# untitled.net
KiCad netlist of a schematic drawn in EAGLE
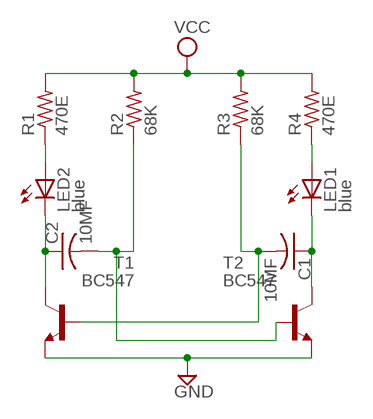
[diagram p0: schematic, sheet 1]

(export (version "E")
  (design (tool "Eeschema 10.0.6"))
  (components
    (comp (ref "C1")
      (value "10MF")
      (footprint "eagle-import:C050-024X044")
      (libsource (lib "eagle-import") (part "C-US050-024X044"))
    )
    (comp (ref "C2")
      (value "10MF")
      (footprint "eagle-import:C050-024X044")
      (libsource (lib "eagle-import") (part "C-US050-024X044"))
    )
    (comp (ref "LED1")
      (value "blue")
      (footprint "eagle-import:LED5MM")
      (libsource (lib "eagle-import") (part "LED5MM"))
    )
    (comp (ref "LED2")
      (value "blue")
      (footprint "eagle-import:LED5MM")
      (libsource (lib "eagle-import") (part "LED5MM"))
    )
    (comp (ref "R1")
      (value "470E")
      (footprint "eagle-import:0207_10")
      (libsource (lib "eagle-import") (part "R-US_0207/10"))
    )
    (comp (ref "R2")
      (value "68K")
      (footprint "eagle-import:0207_10")
      (libsource (lib "eagle-import") (part "R-US_0207/10"))
    )
    (comp (ref "R3")
      (value "68K")
      (footprint "eagle-import:0207_10")
      (libsource (lib "eagle-import") (part "R-US_0207/10"))
    )
    (comp (ref "R4")
      (value "470E")
      (footprint "eagle-import:0207_10")
      (libsource (lib "eagle-import") (part "R-US_0207/10"))
    )
    (comp (ref "T1")
      (value "BC547")
      (footprint "eagle-import:TO92")
      (libsource (lib "eagle-import") (part "BC547"))
    )
    (comp (ref "T2")
      (value "BC547")
      (footprint "eagle-import:TO92")
      (libsource (lib "eagle-import") (part "BC547"))
    )
  )
  (nets
    (net (code "1") (name "GND") (class "Default")
      (node (ref "T1") (pin "1") (pinfunction "E_1") (pintype "passive"))
      (node (ref "T2") (pin "1") (pinfunction "E_1") (pintype "passive"))
    )
    (net (code "2") (name "Net-(LED1-C)") (class "Default")
      (node (ref "C1") (pin "1") (pinfunction "1_1") (pintype "passive"))
      (node (ref "LED1") (pin "K") (pinfunction "C_K") (pintype "passive"))
      (node (ref "T2") (pin "3") (pinfunction "C_3") (pintype "passive"))
    )
    (net (code "3") (name "Net-(LED1-PadA)") (class "Default")
      (node (ref "LED1") (pin "A") (pinfunction "A_A") (pintype "passive"))
      (node (ref "R4") (pin "1") (pinfunction "1_1") (pintype "passive"))
    )
    (net (code "4") (name "Net-(LED2-C)") (class "Default")
      (node (ref "C2") (pin "1") (pinfunction "1_1") (pintype "passive"))
      (node (ref "LED2") (pin "K") (pinfunction "C_K") (pintype "passive"))
      (node (ref "T1") (pin "3") (pinfunction "C_3") (pintype "passive"))
    )
    (net (code "5") (name "Net-(LED2-PadA)") (class "Default")
      (node (ref "LED2") (pin "A") (pinfunction "A_A") (pintype "passive"))
      (node (ref "R1") (pin "1") (pinfunction "1_1") (pintype "passive"))
    )
    (net (code "6") (name "Net-(T1-B)") (class "Default")
      (node (ref "C1") (pin "2") (pinfunction "2_2") (pintype "passive"))
      (node (ref "R3") (pin "1") (pinfunction "1_1") (pintype "passive"))
      (node (ref "T1") (pin "2") (pinfunction "B_2") (pintype "passive"))
    )
    (net (code "7") (name "Net-(T2-B)") (class "Default")
      (node (ref "C2") (pin "2") (pinfunction "2_2") (pintype "passive"))
      (node (ref "R2") (pin "1") (pinfunction "1_1") (pintype "passive"))
      (node (ref "T2") (pin "2") (pinfunction "B_2") (pintype "passive"))
    )
    (net (code "8") (name "VCC") (class "Default")
      (node (ref "R1") (pin "2") (pinfunction "2_2") (pintype "passive"))
      (node (ref "R2") (pin "2") (pinfunction "2_2") (pintype "passive"))
      (node (ref "R3") (pin "2") (pinfunction "2_2") (pintype "passive"))
      (node (ref "R4") (pin "2") (pinfunction "2_2") (pintype "passive"))
    )
  )
)
